# eeZeePowerJack.net
KiCad netlist of a schematic drawn in EAGLE
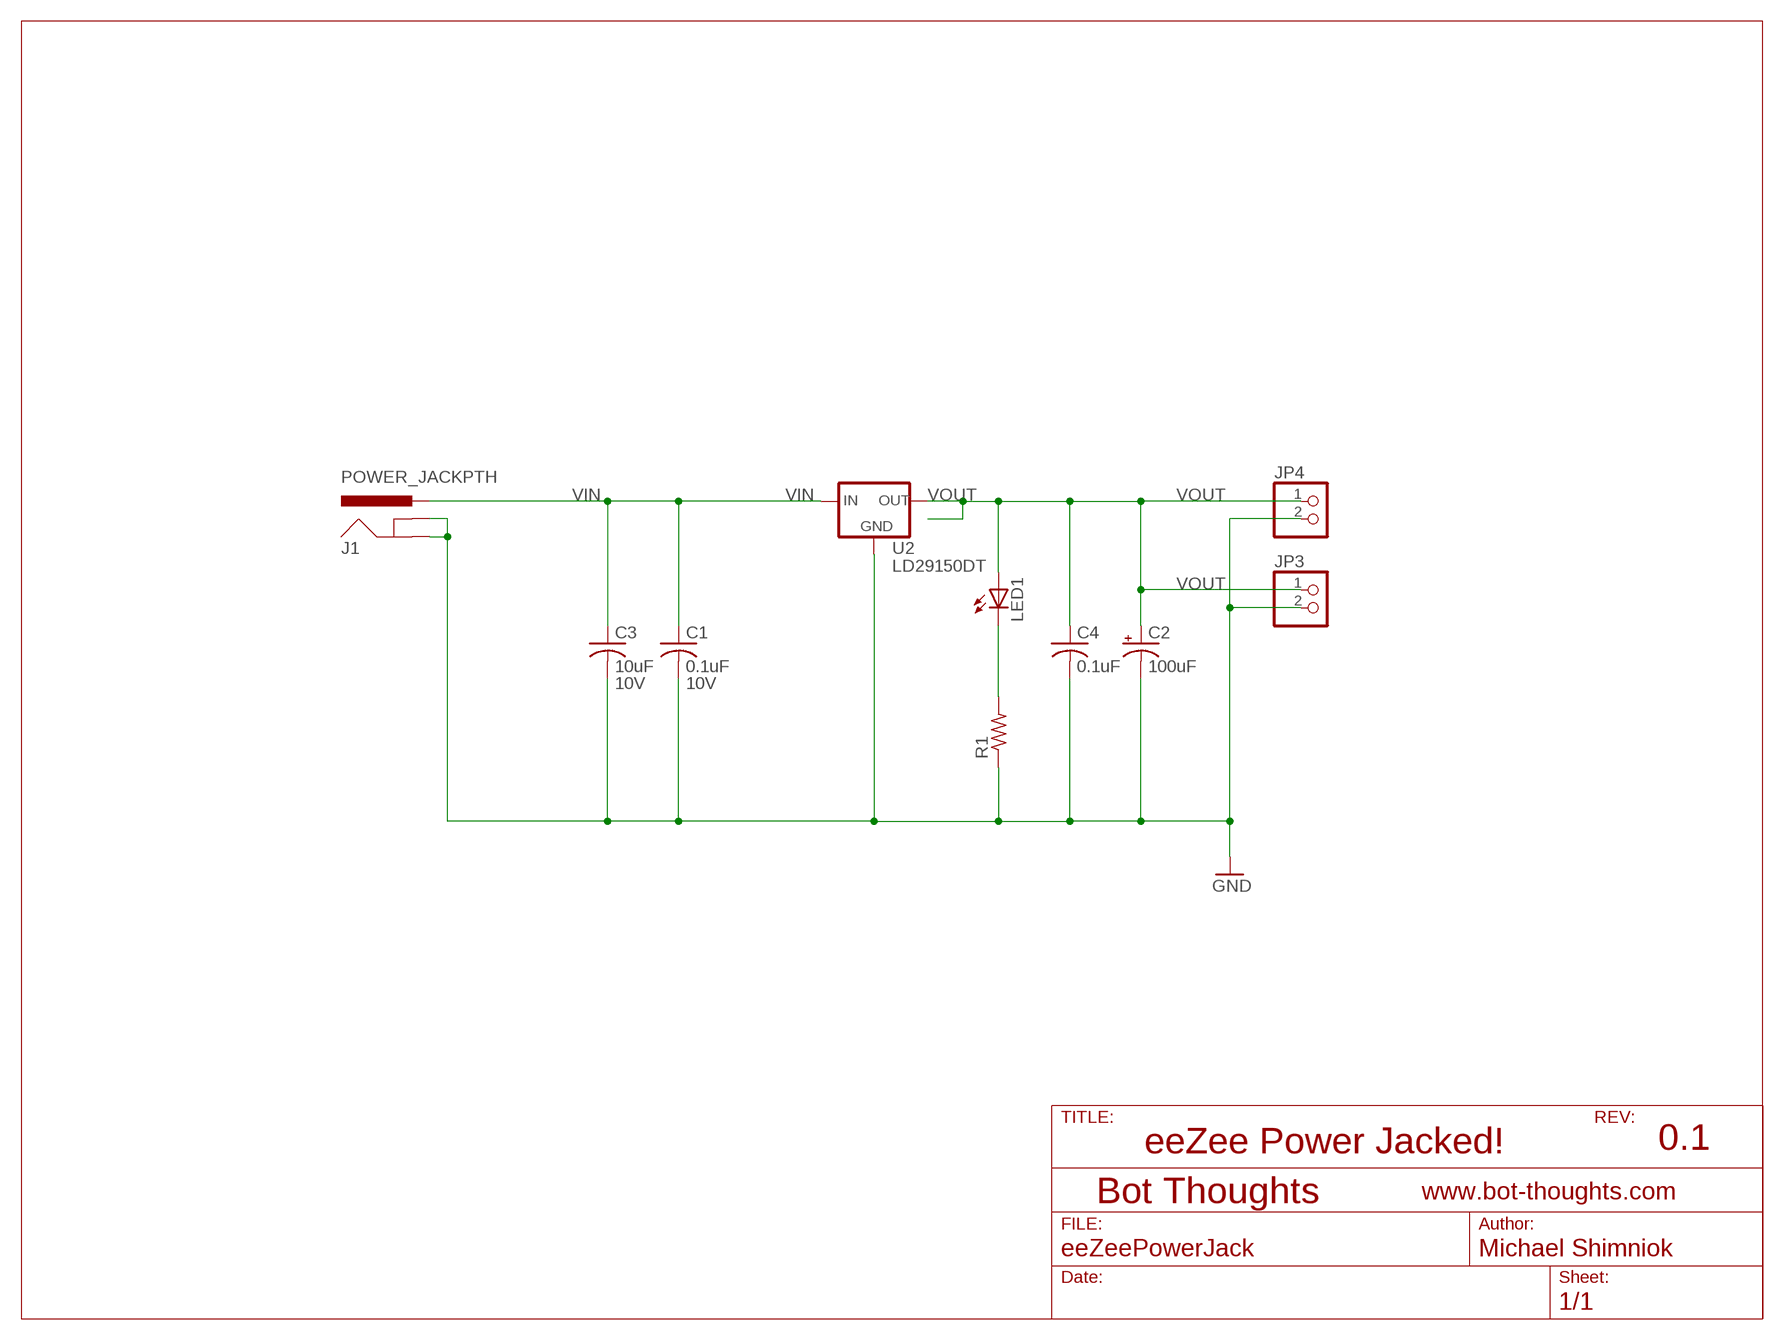
[diagram p0: schematic, sheet 1]

(export (version "E")
  (design (tool "Eeschema 10.0.6"))
  (components
    (comp (ref "C1")
      (value "0.1uF")
      (footprint "eagle-import:C0603")
      (fields (field (name "VOLTAGE") "10V"))
      (libsource (lib "eagle-import") (part "C-USC0603"))
    )
    (comp (ref "C2")
      (value "100uF")
      (footprint "eagle-import:SMC_B")
      (libsource (lib "eagle-import") (part "CPOL-USSMCB"))
    )
    (comp (ref "C3")
      (value "10uF")
      (footprint "eagle-import:C0603")
      (fields (field (name "VOLTAGE") "10V"))
      (libsource (lib "eagle-import") (part "C-USC0603"))
    )
    (comp (ref "C4")
      (value "0.1uF")
      (footprint "eagle-import:C0603")
      (libsource (lib "eagle-import") (part "C-USC0603"))
    )
    (comp (ref "J1")
      (value "POWER_JACKPTH")
      (footprint "eagle-import:POWER_JACK_PTH")
      (libsource (lib "eagle-import") (part "POWER_JACKPTH"))
    )
    (comp (ref "JP3")
      (value "PINHD-1X02_2.54-S")
      (footprint "eagle-import:1X02-S")
      (libsource (lib "eagle-import") (part "PINHD-1X02_2.54-S"))
    )
    (comp (ref "JP4")
      (value "PINHD-1X02_2.54-S")
      (footprint "eagle-import:1X02-S")
      (libsource (lib "eagle-import") (part "PINHD-1X02_2.54-S"))
    )
    (comp (ref "LED1")
      (value "LEDCHIPLED_1206")
      (footprint "eagle-import:CHIPLED_1206")
      (libsource (lib "eagle-import") (part "LEDCHIPLED_1206"))
    )
    (comp (ref "R1")
      (value "R-US_R0603")
      (footprint "eagle-import:R0603")
      (libsource (lib "eagle-import") (part "R-US_R0603"))
    )
    (comp (ref "U2")
      (value "LD29150DT")
      (footprint "eagle-import:DPAK")
      (libsource (lib "eagle-import") (part "LD29150DT"))
    )
  )
  (nets
    (net (code "1") (name "/VIN") (class "Default")
      (node (ref "C1") (pin "1") (pinfunction "1_1") (pintype "passive"))
      (node (ref "C3") (pin "1") (pinfunction "1_1") (pintype "passive"))
      (node (ref "J1") (pin "PWR") (pinfunction "PWR_PWR") (pintype "bidirectional"))
      (node (ref "U2") (pin "1") (pinfunction "VIN_1") (pintype "bidirectional"))
    )
    (net (code "2") (name "/VOUT") (class "Default")
      (node (ref "C2") (pin "+") (pinfunction "+_+") (pintype "passive"))
      (node (ref "C4") (pin "1") (pinfunction "1_1") (pintype "passive"))
      (node (ref "JP3") (pin "1") (pinfunction "1_1") (pintype "passive"))
      (node (ref "JP4") (pin "1") (pinfunction "1_1") (pintype "passive"))
      (node (ref "LED1") (pin "A") (pinfunction "A_A") (pintype "passive"))
      (node (ref "U2") (pin "3") (pinfunction "VOUT_3") (pintype "bidirectional"))
    )
    (net (code "3") (name "GND") (class "Default")
      (node (ref "C1") (pin "2") (pinfunction "2_2") (pintype "passive"))
      (node (ref "C2") (pin "-") (pinfunction "-_-") (pintype "passive"))
      (node (ref "C3") (pin "2") (pinfunction "2_2") (pintype "passive"))
      (node (ref "C4") (pin "2") (pinfunction "2_2") (pintype "passive"))
      (node (ref "J1") (pin "GND") (pinfunction "GND_GND") (pintype "bidirectional"))
      (node (ref "J1") (pin "GNDBREAK") (pinfunction "GNDBREAK_GNDBREAK") (pintype "bidirectional"))
      (node (ref "JP3") (pin "2") (pinfunction "2_2") (pintype "passive"))
      (node (ref "JP4") (pin "2") (pinfunction "2_2") (pintype "passive"))
      (node (ref "R1") (pin "1") (pinfunction "1_1") (pintype "passive"))
      (node (ref "U2") (pin "4") (pinfunction "GND_4") (pintype "bidirectional"))
    )
    (net (code "4") (name "Net-(LED1-PadC)") (class "Default")
      (node (ref "LED1") (pin "C") (pinfunction "C_C") (pintype "passive"))
      (node (ref "R1") (pin "2") (pinfunction "2_2") (pintype "passive"))
    )
  )
)
